# ReboostV2_toplevel.net
KiCad netlist of a schematic drawn in Altium Designer
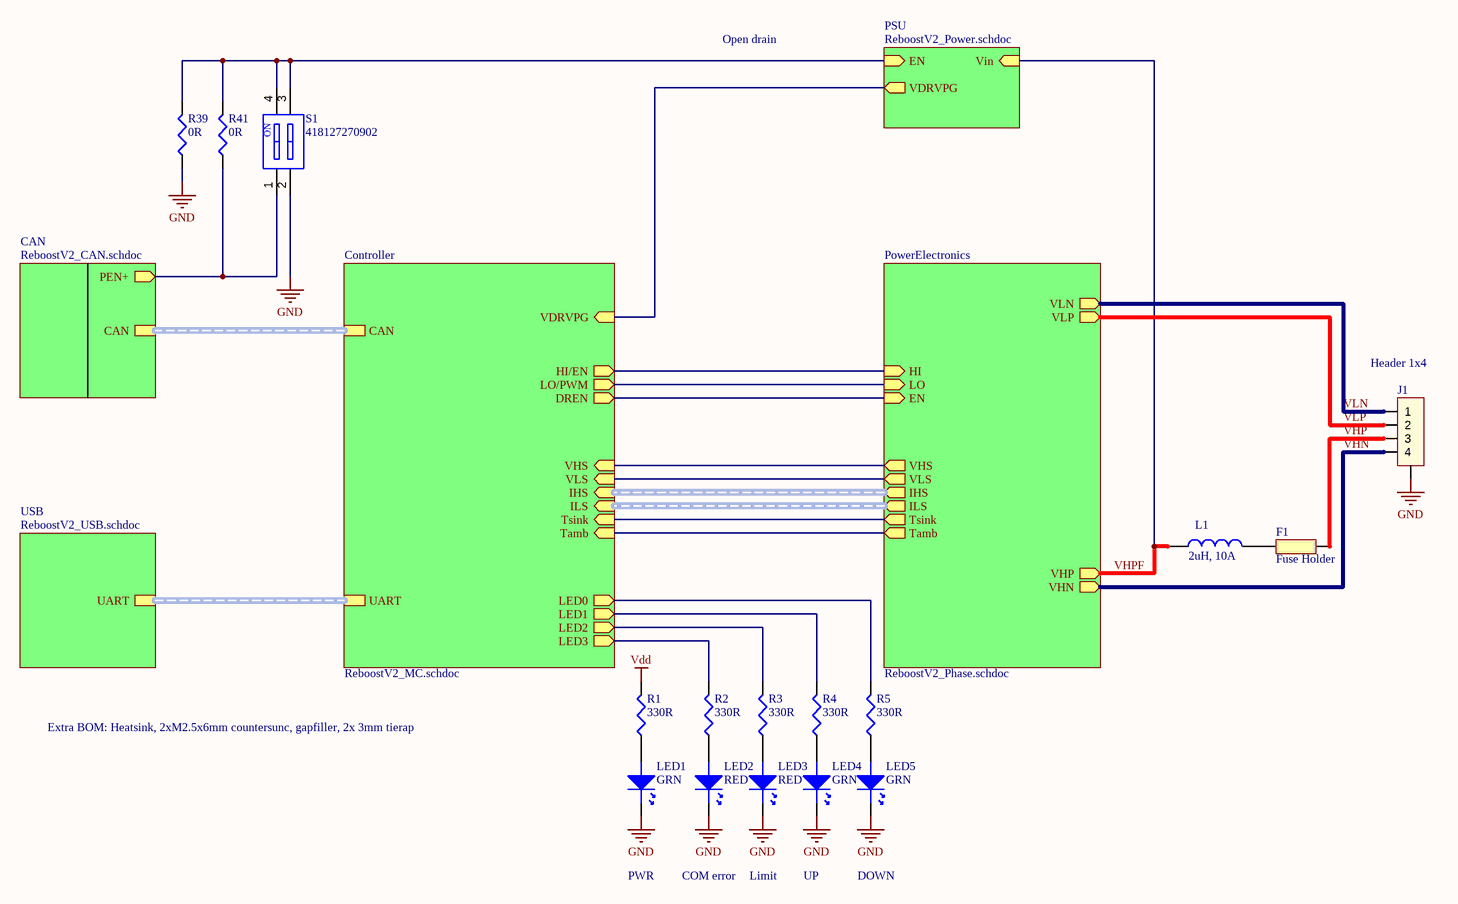
[diagram p0: ReboostV2_toplevel.SchDoc]

(export (version "E")
  (design (tool "Eeschema 10.0.6"))
  (components
    (comp (ref "F1")
      (value "Fuse Holder")
      (footprint "Fuse5x20TH")
      (description "Fuse, Holder, 10A, 250V, T:-40°C +85°C")
      (fields (field (name "MANUFACTURER") "SCHURTER") (field (name "MANUFACTURER PART NUMBER") "0031.8201"))
      (libsource (lib "Reboostv2") (part "0031.8201"))
    )
    (comp (ref "J1")
      (value "Header 1x4")
      (footprint "PC 4/ 4-G-7,62")
      (description "Header, Close Horizontal, 1x4, Male, 7.62mm, TH")
      (fields (field (name "MANUFACTURER") "PHOENIX CONTACT") (field (name "MPN") "PC 4/4-G-7,62"))
      (libsource (lib "Reboostv2") (part "PC 4/4-G-7,62_1"))
    )
    (comp (ref "L1")
      (value "2uH, 10A")
      (footprint "744710210")
      (description "WE-SD Rod Core Choke, 2uH, 10A")
      (fields
        (field (name "MANUFACTURER PART NUMBER") "744710210")
        (field (name "MANUFACTURER") "Wurth Elektronik")
      )
      (libsource (lib "Reboostv2") (part "744710210"))
    )
    (comp (ref "LED1")
      (value "GRN")
      (footprint "WL-SMRW_1206 cylindrical_Reverse use")
      (description "LED, Reverse Mount, Cylindrical, Green")
      (fields
        (field (name "MANUFACTURER") "Wurth Elektronik")
        (field (name "MANUFACTURER PART NUMBER") "156120GS75300")
      )
      (libsource (lib "Reboostv2") (part "156120GS75300"))
    )
    (comp (ref "LED2")
      (value "RED")
      (footprint "WL-SMRW_1206 cylindrical_Reverse use")
      (description "LED, Reverse Mount, Cylindrical, Red")
      (fields
        (field (name "MANUFACTURER") "Wurth Elektronik")
        (field (name "MANUFACTURER PART NUMBER") "156120RS75300")
      )
      (libsource (lib "Reboostv2") (part "156120RS75300"))
    )
    (comp (ref "LED3")
      (value "RED")
      (footprint "WL-SMRW_1206 cylindrical_Reverse use")
      (description "LED, Reverse Mount, Cylindrical, Red")
      (fields
        (field (name "MANUFACTURER") "Wurth Elektronik")
        (field (name "MANUFACTURER PART NUMBER") "156120RS75300")
      )
      (libsource (lib "Reboostv2") (part "156120RS75300"))
    )
    (comp (ref "LED4")
      (value "GRN")
      (footprint "WL-SMRW_1206 cylindrical_Reverse use")
      (description "LED, Reverse Mount, Cylindrical, Green")
      (fields
        (field (name "MANUFACTURER") "Wurth Elektronik")
        (field (name "MANUFACTURER PART NUMBER") "156120GS75300")
      )
      (libsource (lib "Reboostv2") (part "156120GS75300"))
    )
    (comp (ref "LED5")
      (value "GRN")
      (footprint "WL-SMRW_1206 cylindrical_Reverse use")
      (description "LED, Reverse Mount, Cylindrical, Green")
      (fields
        (field (name "MANUFACTURER") "Wurth Elektronik")
        (field (name "MANUFACTURER PART NUMBER") "156120GS75300")
      )
      (libsource (lib "Reboostv2") (part "156120GS75300"))
    )
    (comp (ref "R1")
      (value "330R")
      (footprint "0603")
      (description "Resistor, 330R, 1%, 0.063W, 50V, 100PPM, 0603")
      (fields
        (field (name "MANUFACTURER") "VISHAY DRALORIC")
        (field (name "MANUFACTURER PART NUMBER") "CRCW0603330RFKEA")
      )
      (libsource (lib "Reboostv2") (part "330/0603/0063W/50V"))
    )
    (comp (ref "R2")
      (value "330R")
      (footprint "0603")
      (description "Resistor, 330R, 1%, 0.063W, 50V, 100PPM, 0603")
      (fields
        (field (name "MANUFACTURER") "VISHAY DRALORIC")
        (field (name "MANUFACTURER PART NUMBER") "CRCW0603330RFKEA")
      )
      (libsource (lib "Reboostv2") (part "330/0603/0063W/50V"))
    )
    (comp (ref "R3")
      (value "330R")
      (footprint "0603")
      (description "Resistor, 330R, 1%, 0.063W, 50V, 100PPM, 0603")
      (fields
        (field (name "MANUFACTURER") "VISHAY DRALORIC")
        (field (name "MANUFACTURER PART NUMBER") "CRCW0603330RFKEA")
      )
      (libsource (lib "Reboostv2") (part "330/0603/0063W/50V"))
    )
    (comp (ref "R4")
      (value "330R")
      (footprint "0603")
      (description "Resistor, 330R, 1%, 0.063W, 50V, 100PPM, 0603")
      (fields
        (field (name "MANUFACTURER") "VISHAY DRALORIC")
        (field (name "MANUFACTURER PART NUMBER") "CRCW0603330RFKEA")
      )
      (libsource (lib "Reboostv2") (part "330/0603/0063W/50V"))
    )
    (comp (ref "R5")
      (value "330R")
      (footprint "0603")
      (description "Resistor, 330R, 1%, 0.063W, 50V, 100PPM, 0603")
      (fields
        (field (name "MANUFACTURER") "VISHAY DRALORIC")
        (field (name "MANUFACTURER PART NUMBER") "CRCW0603330RFKEA")
      )
      (libsource (lib "Reboostv2") (part "330/0603/0063W/50V"))
    )
    (comp (ref "R39")
      (value "0R")
      (footprint "0603")
      (description "Resistor, 0R, 0.1%, 0.063W, 50V, 200PPM, 0603")
      (fields
        (field (name "MANUFACTURER") "VISHAY DRALORIC")
        (field (name "MANUFACTURER PART NUMBER") "CRCW06030000Z0EA")
      )
      (libsource (lib "Reboostv2") (part "0/0603/0063W/50V"))
    )
    (comp (ref "R41")
      (value "0R")
      (footprint "0603")
      (description "Resistor, 0R, 0.1%, 0.063W, 50V, 200PPM, 0603")
      (fields
        (field (name "MANUFACTURER") "VISHAY DRALORIC")
        (field (name "MANUFACTURER PART NUMBER") "CRCW06030000Z0EA")
      )
      (libsource (lib "Reboostv2") (part "0/0603/0063W/50V"))
    )
    (comp (ref "S1")
      (value "418127270902")
      (footprint "418127270902")
      (description "WS-DITV Small Compact THT Dip Switch, Raised Actuator, pitch 2.54mm, 2p")
      (fields (field (name "MANUFACTURER") "Wurth Elektronik") (field (name "PUBLISHER") "Wurth Elektronik"))
      (libsource (lib "Reboostv2") (part "418127270902"))
    )
  )
  (nets
    (net (code "3") (name "/EN") (class "Default")
      (node (ref "R39") (pin "2") (pinfunction "2_2") (pintype "passive"))
      (node (ref "R41") (pin "2") (pinfunction "2_2") (pintype "passive"))
      (node (ref "S1") (pin "3") (pinfunction "3_3") (pintype "passive"))
      (node (ref "S1") (pin "4") (pinfunction "4_4") (pintype "passive"))
    )
    (net (code "7") (name "/LED0") (class "Default")
      (node (ref "R5") (pin "2") (pinfunction "2_2") (pintype "passive"))
    )
    (net (code "8") (name "/LED1") (class "Default")
      (node (ref "R4") (pin "2") (pinfunction "2_2") (pintype "passive"))
    )
    (net (code "9") (name "/LED2") (class "Default")
      (node (ref "R3") (pin "2") (pinfunction "2_2") (pintype "passive"))
    )
    (net (code "10") (name "/LED3") (class "Default")
      (node (ref "R2") (pin "2") (pinfunction "2_2") (pintype "passive"))
    )
    (net (code "12") (name "/PEN+") (class "Default")
      (node (ref "R41") (pin "1") (pinfunction "1_1") (pintype "passive"))
      (node (ref "S1") (pin "1") (pinfunction "1_1") (pintype "passive"))
    )
    (net (code "17") (name "/VHN") (class "Default")
      (node (ref "J1") (pin "4") (pinfunction "4_4") (pintype "passive"))
    )
    (net (code "18") (name "/VHP") (class "Default")
      (node (ref "F1") (pin "2") (pinfunction "2_2") (pintype "passive"))
      (node (ref "J1") (pin "3") (pinfunction "3_3") (pintype "passive"))
    )
    (net (code "19") (name "/VHPF") (class "Default")
      (node (ref "L1") (pin "1") (pinfunction "1_1") (pintype "passive"))
    )
    (net (code "21") (name "/VLN") (class "Default")
      (node (ref "J1") (pin "1") (pinfunction "1_1") (pintype "passive"))
    )
    (net (code "22") (name "/VLP") (class "Default")
      (node (ref "J1") (pin "2") (pinfunction "2_2") (pintype "passive"))
    )
    (net (code "24") (name "GND") (class "Default")
      (node (ref "J1") (pin "0") (pinfunction "0_0") (pintype "passive"))
      (node (ref "LED1") (pin "1") (pinfunction "K_1") (pintype "passive"))
      (node (ref "LED2") (pin "1") (pinfunction "K_1") (pintype "passive"))
      (node (ref "LED3") (pin "1") (pinfunction "K_1") (pintype "passive"))
      (node (ref "LED4") (pin "1") (pinfunction "K_1") (pintype "passive"))
      (node (ref "LED5") (pin "1") (pinfunction "K_1") (pintype "passive"))
      (node (ref "R39") (pin "1") (pinfunction "1_1") (pintype "passive"))
      (node (ref "S1") (pin "2") (pinfunction "2_2") (pintype "passive"))
    )
    (net (code "25") (name "Net-(F1-Pad1)") (class "Default")
      (node (ref "F1") (pin "1") (pinfunction "1_1") (pintype "passive"))
      (node (ref "L1") (pin "2") (pinfunction "2_2") (pintype "passive"))
    )
    (net (code "26") (name "Net-(LED1-A)") (class "Default")
      (node (ref "LED1") (pin "2") (pinfunction "A_2") (pintype "passive"))
      (node (ref "R1") (pin "1") (pinfunction "1_1") (pintype "passive"))
    )
    (net (code "27") (name "Net-(LED2-A)") (class "Default")
      (node (ref "LED2") (pin "2") (pinfunction "A_2") (pintype "passive"))
      (node (ref "R2") (pin "1") (pinfunction "1_1") (pintype "passive"))
    )
    (net (code "28") (name "Net-(LED3-A)") (class "Default")
      (node (ref "LED3") (pin "2") (pinfunction "A_2") (pintype "passive"))
      (node (ref "R3") (pin "1") (pinfunction "1_1") (pintype "passive"))
    )
    (net (code "29") (name "Net-(LED4-A)") (class "Default")
      (node (ref "LED4") (pin "2") (pinfunction "A_2") (pintype "passive"))
      (node (ref "R4") (pin "1") (pinfunction "1_1") (pintype "passive"))
    )
    (net (code "30") (name "Net-(LED5-A)") (class "Default")
      (node (ref "LED5") (pin "2") (pinfunction "A_2") (pintype "passive"))
      (node (ref "R5") (pin "1") (pinfunction "1_1") (pintype "passive"))
    )
    (net (code "31") (name "Vdd") (class "Default")
      (node (ref "R1") (pin "2") (pinfunction "2_2") (pintype "passive"))
    )
  )
)
